# Stack_Header.net
KiCad netlist of a schematic drawn in Altium Designer
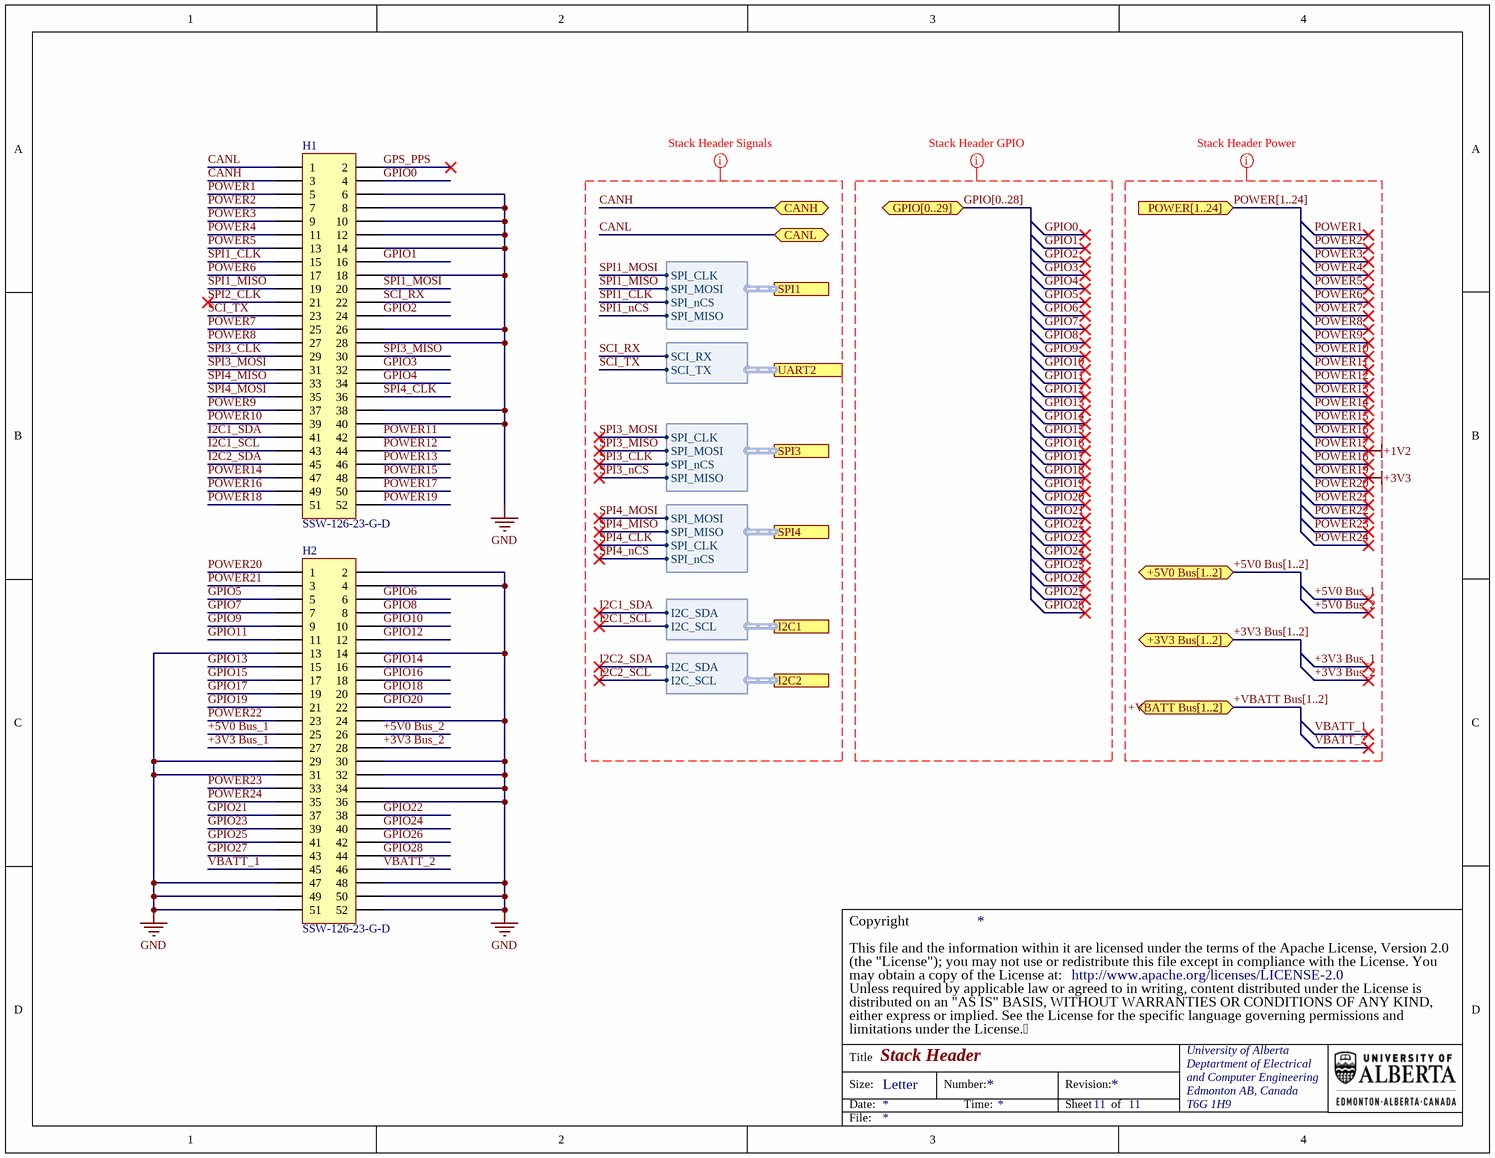
[diagram p0: Stack Header.SchDoc]

(export (version "E")
  (design (tool "Eeschema 10.0.6"))
  (components
    (comp (ref "H1")
      (value "SSW-126-23-G-D")
      (footprint "SSW-126-23-G-D")
      (fields (field (name "PART NUMBER") "PP-SAM-00002") (field (name "PUBLISHER") "AlbertaSat"))
      (libsource (lib "Database") (part "Header 26X2"))
    )
    (comp (ref "H2")
      (value "SSW-126-23-G-D")
      (footprint "SSW-126-23-G-D")
      (fields (field (name "PART NUMBER") "PP-SAM-00002") (field (name "PUBLISHER") "AlbertaSat"))
      (libsource (lib "Database") (part "Header 26X2"))
    )
  )
  (nets
    (net (code "7") (name "+1V2") (class "Default")
      (node (ref "H1") (pin "50") (pinfunction "50_50") (pintype "passive"))
    )
    (net (code "8") (name "+3V3") (class "Default")
      (node (ref "H1") (pin "52") (pinfunction "52_52") (pintype "passive"))
    )
    (net (code "9") (name "/+3V3 Bus_1") (class "Default")
      (node (ref "H2") (pin "27") (pinfunction "27_27") (pintype "passive+no_connect"))
    )
    (net (code "10") (name "/+3V3 Bus_2") (class "Default")
      (node (ref "H2") (pin "28") (pinfunction "28_28") (pintype "passive+no_connect"))
    )
    (net (code "11") (name "/+5V0 Bus_1") (class "Default")
      (node (ref "H2") (pin "25") (pinfunction "25_25") (pintype "passive+no_connect"))
    )
    (net (code "12") (name "/+5V0 Bus_2") (class "Default")
      (node (ref "H2") (pin "26") (pinfunction "26_26") (pintype "passive+no_connect"))
    )
    (net (code "13") (name "/CANH") (class "Default")
      (node (ref "H1") (pin "3") (pinfunction "3_3") (pintype "passive"))
    )
    (net (code "14") (name "/CANL") (class "Default")
      (node (ref "H1") (pin "1") (pinfunction "1_1") (pintype "passive"))
    )
    (net (code "15") (name "/GPIO0") (class "Default")
      (node (ref "H1") (pin "4") (pinfunction "4_4") (pintype "passive"))
    )
    (net (code "16") (name "/GPIO1") (class "Default")
      (node (ref "H1") (pin "16") (pinfunction "16_16") (pintype "passive"))
    )
    (net (code "17") (name "/GPIO2") (class "Default")
      (node (ref "H1") (pin "24") (pinfunction "24_24") (pintype "passive"))
    )
    (net (code "18") (name "/GPIO3") (class "Default")
      (node (ref "H1") (pin "32") (pinfunction "32_32") (pintype "passive"))
    )
    (net (code "19") (name "/GPIO4") (class "Default")
      (node (ref "H1") (pin "34") (pinfunction "34_34") (pintype "passive"))
    )
    (net (code "20") (name "/GPIO5") (class "Default")
      (node (ref "H2") (pin "5") (pinfunction "5_5") (pintype "passive"))
    )
    (net (code "21") (name "/GPIO6") (class "Default")
      (node (ref "H2") (pin "6") (pinfunction "6_6") (pintype "passive"))
    )
    (net (code "22") (name "/GPIO7") (class "Default")
      (node (ref "H2") (pin "7") (pinfunction "7_7") (pintype "passive"))
    )
    (net (code "23") (name "/GPIO8") (class "Default")
      (node (ref "H2") (pin "8") (pinfunction "8_8") (pintype "passive"))
    )
    (net (code "24") (name "/GPIO9") (class "Default")
      (node (ref "H2") (pin "9") (pinfunction "9_9") (pintype "passive"))
    )
    (net (code "25") (name "/GPIO10") (class "Default")
      (node (ref "H2") (pin "10") (pinfunction "10_10") (pintype "passive"))
    )
    (net (code "26") (name "/GPIO11") (class "Default")
      (node (ref "H2") (pin "11") (pinfunction "11_11") (pintype "passive"))
    )
    (net (code "27") (name "/GPIO12") (class "Default")
      (node (ref "H2") (pin "12") (pinfunction "12_12") (pintype "passive"))
    )
    (net (code "28") (name "/GPIO13") (class "Default")
      (node (ref "H2") (pin "15") (pinfunction "15_15") (pintype "passive"))
    )
    (net (code "29") (name "/GPIO14") (class "Default")
      (node (ref "H2") (pin "16") (pinfunction "16_16") (pintype "passive"))
    )
    (net (code "30") (name "/GPIO15") (class "Default")
      (node (ref "H2") (pin "17") (pinfunction "17_17") (pintype "passive+no_connect"))
    )
    (net (code "31") (name "/GPIO16") (class "Default")
      (node (ref "H2") (pin "18") (pinfunction "18_18") (pintype "passive+no_connect"))
    )
    (net (code "32") (name "/GPIO17") (class "Default")
      (node (ref "H2") (pin "19") (pinfunction "19_19") (pintype "passive+no_connect"))
    )
    (net (code "33") (name "/GPIO18") (class "Default")
      (node (ref "H2") (pin "20") (pinfunction "20_20") (pintype "passive+no_connect"))
    )
    (net (code "34") (name "/GPIO19") (class "Default")
      (node (ref "H2") (pin "21") (pinfunction "21_21") (pintype "passive+no_connect"))
    )
    (net (code "35") (name "/GPIO20") (class "Default")
      (node (ref "H2") (pin "22") (pinfunction "22_22") (pintype "passive+no_connect"))
    )
    (net (code "36") (name "/GPIO21") (class "Default")
      (node (ref "H2") (pin "37") (pinfunction "37_37") (pintype "passive+no_connect"))
    )
    (net (code "37") (name "/GPIO22") (class "Default")
      (node (ref "H2") (pin "38") (pinfunction "38_38") (pintype "passive+no_connect"))
    )
    (net (code "38") (name "/GPIO23") (class "Default")
      (node (ref "H2") (pin "39") (pinfunction "39_39") (pintype "passive+no_connect"))
    )
    (net (code "39") (name "/GPIO24") (class "Default")
      (node (ref "H2") (pin "40") (pinfunction "40_40") (pintype "passive+no_connect"))
    )
    (net (code "40") (name "/GPIO25") (class "Default")
      (node (ref "H2") (pin "41") (pinfunction "41_41") (pintype "passive+no_connect"))
    )
    (net (code "41") (name "/GPIO26") (class "Default")
      (node (ref "H2") (pin "42") (pinfunction "42_42") (pintype "passive+no_connect"))
    )
    (net (code "42") (name "/GPIO27") (class "Default")
      (node (ref "H2") (pin "43") (pinfunction "43_43") (pintype "passive+no_connect"))
    )
    (net (code "43") (name "/GPIO28") (class "Default")
      (node (ref "H2") (pin "44") (pinfunction "44_44") (pintype "passive+no_connect"))
    )
    (net (code "45") (name "/GPS_PPS") (class "Default")
      (node (ref "H1") (pin "2") (pinfunction "2_2") (pintype "passive+no_connect"))
    )
    (net (code "46") (name "/I2C1_SCL") (class "Default")
      (node (ref "H1") (pin "43") (pinfunction "43_43") (pintype "passive+no_connect"))
    )
    (net (code "47") (name "/I2C1_SDA") (class "Default")
      (node (ref "H1") (pin "41") (pinfunction "41_41") (pintype "passive+no_connect"))
    )
    (net (code "49") (name "/I2C2_SDA") (class "Default")
      (node (ref "H1") (pin "45") (pinfunction "45_45") (pintype "passive+no_connect"))
    )
    (net (code "50") (name "/POWER1") (class "Default")
      (node (ref "H1") (pin "5") (pinfunction "5_5") (pintype "passive"))
    )
    (net (code "51") (name "/POWER2") (class "Default")
      (node (ref "H1") (pin "7") (pinfunction "7_7") (pintype "passive"))
    )
    (net (code "52") (name "/POWER3") (class "Default")
      (node (ref "H1") (pin "9") (pinfunction "9_9") (pintype "passive"))
    )
    (net (code "53") (name "/POWER4") (class "Default")
      (node (ref "H1") (pin "11") (pinfunction "11_11") (pintype "passive"))
    )
    (net (code "54") (name "/POWER5") (class "Default")
      (node (ref "H1") (pin "13") (pinfunction "13_13") (pintype "passive"))
    )
    (net (code "55") (name "/POWER6") (class "Default")
      (node (ref "H1") (pin "17") (pinfunction "17_17") (pintype "passive+no_connect"))
    )
    (net (code "56") (name "/POWER7") (class "Default")
      (node (ref "H1") (pin "25") (pinfunction "25_25") (pintype "passive+no_connect"))
    )
    (net (code "57") (name "/POWER8") (class "Default")
      (node (ref "H1") (pin "27") (pinfunction "27_27") (pintype "passive+no_connect"))
    )
    (net (code "58") (name "/POWER9") (class "Default")
      (node (ref "H1") (pin "37") (pinfunction "37_37") (pintype "passive+no_connect"))
    )
    (net (code "59") (name "/POWER10") (class "Default")
      (node (ref "H1") (pin "39") (pinfunction "39_39") (pintype "passive+no_connect"))
    )
    (net (code "60") (name "/POWER11") (class "Default")
      (node (ref "H1") (pin "42") (pinfunction "42_42") (pintype "passive+no_connect"))
    )
    (net (code "61") (name "/POWER12") (class "Default")
      (node (ref "H1") (pin "44") (pinfunction "44_44") (pintype "passive+no_connect"))
    )
    (net (code "62") (name "/POWER13") (class "Default")
      (node (ref "H1") (pin "46") (pinfunction "46_46") (pintype "passive+no_connect"))
    )
    (net (code "63") (name "/POWER14") (class "Default")
      (node (ref "H1") (pin "47") (pinfunction "47_47") (pintype "passive+no_connect"))
    )
    (net (code "64") (name "/POWER15") (class "Default")
      (node (ref "H1") (pin "48") (pinfunction "48_48") (pintype "passive+no_connect"))
    )
    (net (code "65") (name "/POWER16") (class "Default")
      (node (ref "H1") (pin "49") (pinfunction "49_49") (pintype "passive+no_connect"))
    )
    (net (code "66") (name "/POWER18") (class "Default")
      (node (ref "H1") (pin "51") (pinfunction "51_51") (pintype "passive+no_connect"))
    )
    (net (code "67") (name "/POWER20") (class "Default")
      (node (ref "H2") (pin "1") (pinfunction "1_1") (pintype "passive+no_connect"))
    )
    (net (code "68") (name "/POWER21") (class "Default")
      (node (ref "H2") (pin "3") (pinfunction "3_3") (pintype "passive+no_connect"))
    )
    (net (code "69") (name "/POWER22") (class "Default")
      (node (ref "H2") (pin "23") (pinfunction "23_23") (pintype "passive+no_connect"))
    )
    (net (code "70") (name "/POWER23") (class "Default")
      (node (ref "H2") (pin "33") (pinfunction "33_33") (pintype "passive+no_connect"))
    )
    (net (code "71") (name "/POWER24") (class "Default")
      (node (ref "H2") (pin "35") (pinfunction "35_35") (pintype "passive+no_connect"))
    )
    (net (code "73") (name "/SCI_RX") (class "Default")
      (node (ref "H1") (pin "22") (pinfunction "22_22") (pintype "passive"))
    )
    (net (code "74") (name "/SCI_TX") (class "Default")
      (node (ref "H1") (pin "23") (pinfunction "23_23") (pintype "passive"))
    )
    (net (code "75") (name "/SPI1_CLK") (class "Default")
      (node (ref "H1") (pin "15") (pinfunction "15_15") (pintype "passive"))
    )
    (net (code "76") (name "/SPI1_MISO") (class "Default")
      (node (ref "H1") (pin "19") (pinfunction "19_19") (pintype "passive"))
    )
    (net (code "77") (name "/SPI1_MOSI") (class "Default")
      (node (ref "H1") (pin "20") (pinfunction "20_20") (pintype "passive"))
    )
    (net (code "79") (name "/SPI2_CLK") (class "Default")
      (node (ref "H1") (pin "21") (pinfunction "21_21") (pintype "passive+no_connect"))
    )
    (net (code "80") (name "/SPI3_CLK") (class "Default")
      (node (ref "H1") (pin "29") (pinfunction "29_29") (pintype "passive+no_connect"))
    )
    (net (code "81") (name "/SPI3_MISO") (class "Default")
      (node (ref "H1") (pin "30") (pinfunction "30_30") (pintype "passive+no_connect"))
    )
    (net (code "82") (name "/SPI3_MOSI") (class "Default")
      (node (ref "H1") (pin "31") (pinfunction "31_31") (pintype "passive+no_connect"))
    )
    (net (code "84") (name "/SPI4_CLK") (class "Default")
      (node (ref "H1") (pin "36") (pinfunction "36_36") (pintype "passive+no_connect"))
    )
    (net (code "85") (name "/SPI4_MISO") (class "Default")
      (node (ref "H1") (pin "33") (pinfunction "33_33") (pintype "passive+no_connect"))
    )
    (net (code "86") (name "/SPI4_MOSI") (class "Default")
      (node (ref "H1") (pin "35") (pinfunction "35_35") (pintype "passive+no_connect"))
    )
    (net (code "88") (name "/VBATT_1") (class "Default")
      (node (ref "H2") (pin "45") (pinfunction "45_45") (pintype "passive+no_connect"))
    )
    (net (code "89") (name "/VBATT_2") (class "Default")
      (node (ref "H2") (pin "46") (pinfunction "46_46") (pintype "passive+no_connect"))
    )
    (net (code "99") (name "GND") (class "Default")
      (node (ref "H1") (pin "10") (pinfunction "10_10") (pintype "passive"))
      (node (ref "H1") (pin "12") (pinfunction "12_12") (pintype "passive"))
      (node (ref "H1") (pin "14") (pinfunction "14_14") (pintype "passive"))
      (node (ref "H1") (pin "18") (pinfunction "18_18") (pintype "passive"))
      (node (ref "H1") (pin "26") (pinfunction "26_26") (pintype "passive"))
      (node (ref "H1") (pin "28") (pinfunction "28_28") (pintype "passive"))
      (node (ref "H1") (pin "38") (pinfunction "38_38") (pintype "passive"))
      (node (ref "H1") (pin "40") (pinfunction "40_40") (pintype "passive"))
      (node (ref "H1") (pin "6") (pinfunction "6_6") (pintype "passive"))
      (node (ref "H1") (pin "8") (pinfunction "8_8") (pintype "passive"))
      (node (ref "H2") (pin "13") (pinfunction "13_13") (pintype "passive"))
      (node (ref "H2") (pin "14") (pinfunction "14_14") (pintype "passive"))
      (node (ref "H2") (pin "2") (pinfunction "2_2") (pintype "passive"))
      (node (ref "H2") (pin "24") (pinfunction "24_24") (pintype "passive"))
      (node (ref "H2") (pin "29") (pinfunction "29_29") (pintype "passive"))
      (node (ref "H2") (pin "30") (pinfunction "30_30") (pintype "passive"))
      (node (ref "H2") (pin "31") (pinfunction "31_31") (pintype "passive"))
      (node (ref "H2") (pin "32") (pinfunction "32_32") (pintype "passive"))
      (node (ref "H2") (pin "34") (pinfunction "34_34") (pintype "passive"))
      (node (ref "H2") (pin "36") (pinfunction "36_36") (pintype "passive"))
      (node (ref "H2") (pin "4") (pinfunction "4_4") (pintype "passive"))
      (node (ref "H2") (pin "47") (pinfunction "47_47") (pintype "passive"))
      (node (ref "H2") (pin "48") (pinfunction "48_48") (pintype "passive"))
      (node (ref "H2") (pin "49") (pinfunction "49_49") (pintype "passive"))
      (node (ref "H2") (pin "50") (pinfunction "50_50") (pintype "passive"))
      (node (ref "H2") (pin "51") (pinfunction "51_51") (pintype "passive"))
      (node (ref "H2") (pin "52") (pinfunction "52_52") (pintype "passive"))
    )
  )
)
